# driver_piezo.net
KiCad netlist of a schematic drawn in EAGLE
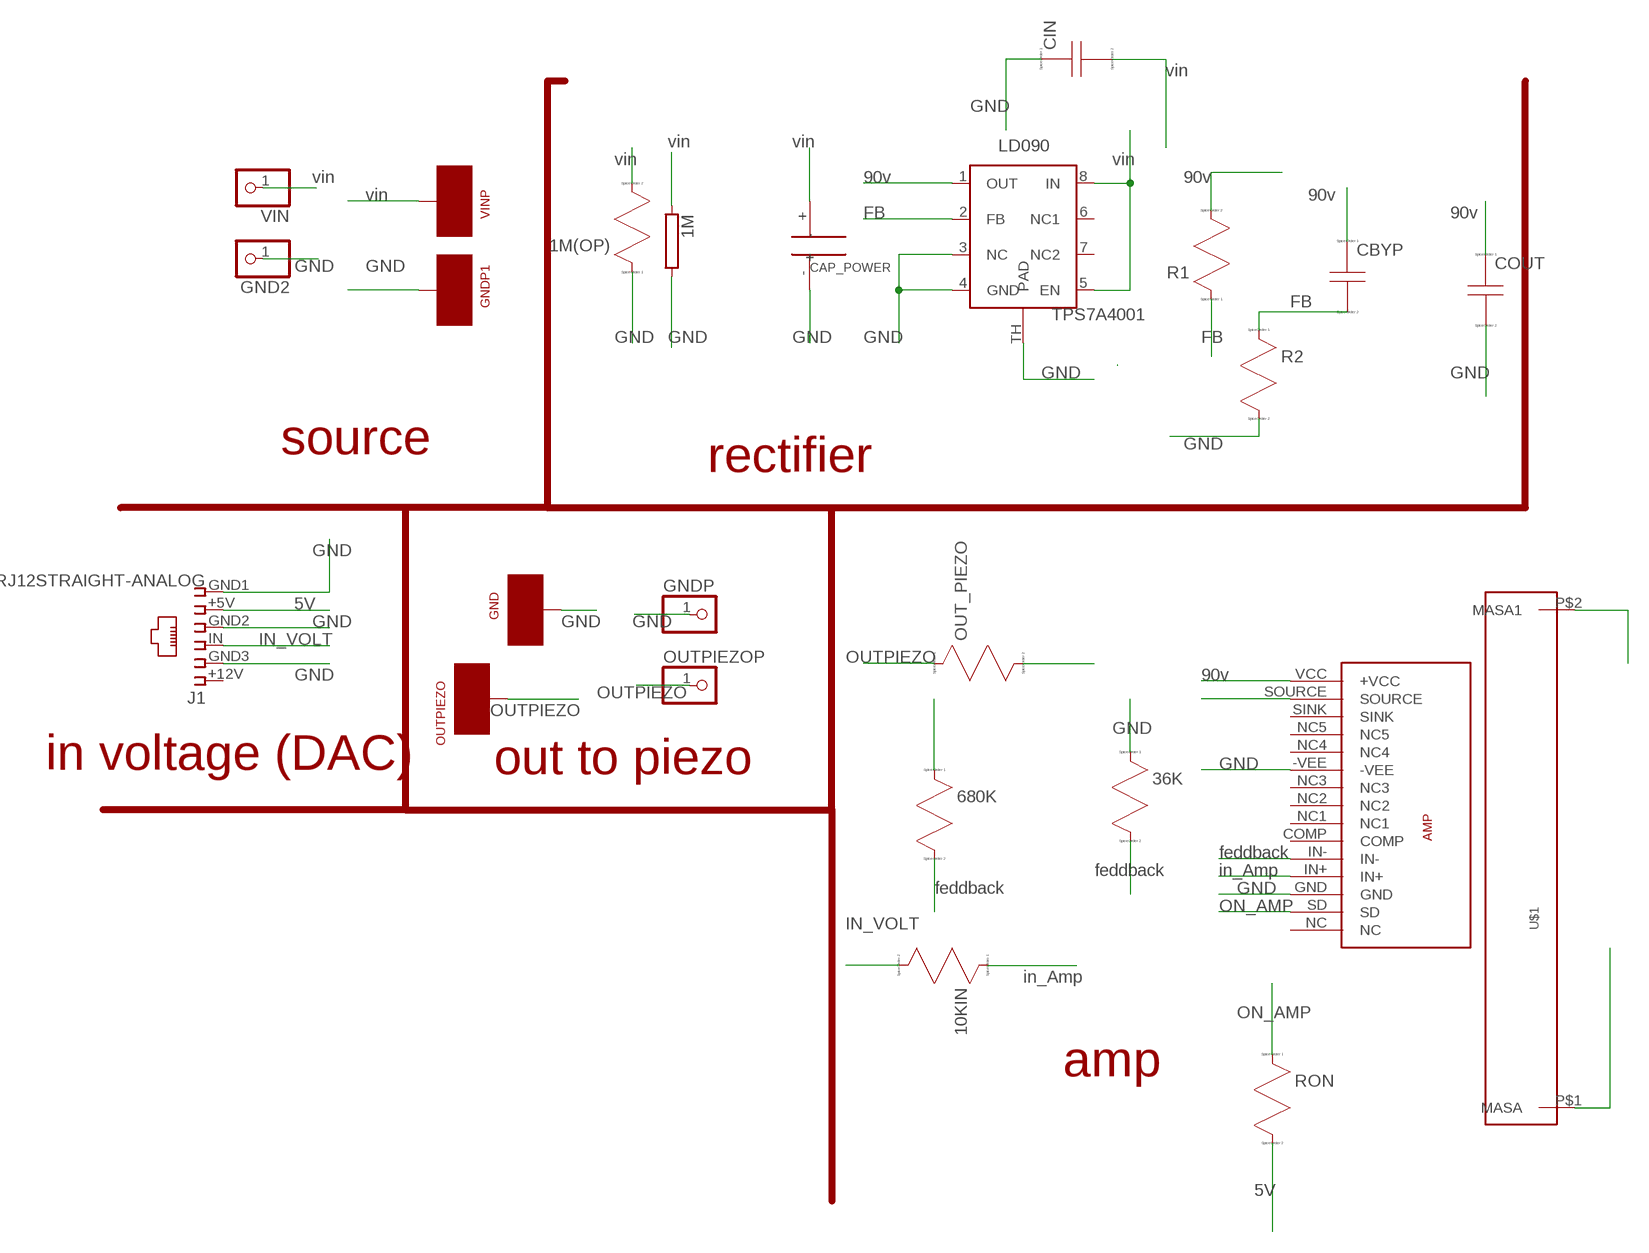
[diagram p0: schematic, sheet 1]

(export (version "E")
  (design (tool "Eeschema 10.0.6"))
  (components
    (comp (ref "1M")
      (value "RCA0002")
      (footprint "eagle-import:CA0002")
      (libsource (lib "eagle-import") (part "RCA0002"))
    )
    (comp (ref "1M(OP)")
      (value "RES")
      (footprint "eagle-import:R0805")
      (libsource (lib "eagle-import") (part "RES"))
    )
    (comp (ref "10KIN")
      (value "RES")
      (footprint "eagle-import:R0805")
      (libsource (lib "eagle-import") (part "RES"))
    )
    (comp (ref "36K")
      (value "RES")
      (footprint "eagle-import:R0805")
      (libsource (lib "eagle-import") (part "RES"))
    )
    (comp (ref "680K")
      (value "RES")
      (footprint "eagle-import:R0805")
      (libsource (lib "eagle-import") (part "RES"))
    )
    (comp (ref "AMP")
      (value "POWER_AMP_LME49811TB")
      (footprint "eagle-import:POWER_AMP_LME49811TB")
      (libsource (lib "eagle-import") (part "POWER_AMP_LME49811TB"))
    )
    (comp (ref "CAP_POWER")
      (value "CAP200VCAP200V")
      (footprint "eagle-import:CAP200V")
      (libsource (lib "eagle-import") (part "CAP200VCAP200V"))
    )
    (comp (ref "CBYP")
      (value "CAP")
      (footprint "eagle-import:C0805")
      (libsource (lib "eagle-import") (part "CAP"))
    )
    (comp (ref "CIN")
      (value "CAP")
      (footprint "eagle-import:C0805")
      (libsource (lib "eagle-import") (part "CAP"))
    )
    (comp (ref "COUT")
      (value "CAP")
      (footprint "eagle-import:C0805")
      (libsource (lib "eagle-import") (part "CAP"))
    )
    (comp (ref "GND")
      (value "PAD")
      (footprint "eagle-import:PAD")
      (libsource (lib "eagle-import") (part "PAD"))
    )
    (comp (ref "GND2")
      (value "PINHD-1X1")
      (footprint "eagle-import:1X01")
      (libsource (lib "eagle-import") (part "PINHD-1X1"))
    )
    (comp (ref "GNDP")
      (value "PINHD-1X1")
      (footprint "eagle-import:1X01")
      (libsource (lib "eagle-import") (part "PINHD-1X1"))
    )
    (comp (ref "GNDP1")
      (value "PAD")
      (footprint "eagle-import:PAD")
      (libsource (lib "eagle-import") (part "PAD"))
    )
    (comp (ref "J1")
      (value "RJ12STRAIGHT-ANALOG")
      (footprint "eagle-import:RJ12-STRAIGHT-ANALOG")
      (libsource (lib "eagle-import") (part "RJ12STRAIGHT-ANALOG"))
    )
    (comp (ref "LD090")
      (value "TPS7A4001")
      (footprint "eagle-import:S-PDSO-G08")
      (libsource (lib "eagle-import") (part "TPS7A4001"))
    )
    (comp (ref "OUTPIEZO")
      (value "PAD")
      (footprint "eagle-import:PAD")
      (libsource (lib "eagle-import") (part "PAD"))
    )
    (comp (ref "OUTPIEZOP")
      (value "PINHD-1X1")
      (footprint "eagle-import:1X01")
      (libsource (lib "eagle-import") (part "PINHD-1X1"))
    )
    (comp (ref "OUT_PIEZO")
      (value "RES")
      (footprint "eagle-import:R0805")
      (libsource (lib "eagle-import") (part "RES"))
    )
    (comp (ref "R1")
      (value "RES")
      (footprint "eagle-import:R0805")
      (libsource (lib "eagle-import") (part "RES"))
    )
    (comp (ref "R2")
      (value "RES")
      (footprint "eagle-import:R0805")
      (libsource (lib "eagle-import") (part "RES"))
    )
    (comp (ref "RON")
      (value "RES")
      (footprint "eagle-import:R0805")
      (libsource (lib "eagle-import") (part "RES"))
    )
    (comp (ref "U$1")
      (value "DISIPADOR")
      (footprint "eagle-import:DISIPADOR")
      (libsource (lib "eagle-import") (part "DISIPADOR"))
    )
    (comp (ref "VIN")
      (value "PINHD-1X1")
      (footprint "eagle-import:1X01")
      (libsource (lib "eagle-import") (part "PINHD-1X1"))
    )
    (comp (ref "VINP")
      (value "PAD")
      (footprint "eagle-import:PAD")
      (libsource (lib "eagle-import") (part "PAD"))
    )
  )
  (nets
    (net (code "1") (name "/5V") (class "Default")
      (node (ref "J1") (pin "+5V") (pinfunction "5_+5V") (pintype "bidirectional"))
      (node (ref "RON") (pin "2") (pinfunction "B_2") (pintype "passive"))
    )
    (net (code "2") (name "/B") (class "Default")
      (node (ref "36K") (pin "2") (pinfunction "B_2") (pintype "passive"))
      (node (ref "680K") (pin "2") (pinfunction "B_2") (pintype "passive"))
      (node (ref "AMP") (pin "IN-") (pinfunction "IN-_IN-") (pintype "bidirectional"))
    )
    (net (code "3") (name "/FB") (class "Default")
      (node (ref "CBYP") (pin "2") (pinfunction "B_2") (pintype "passive"))
      (node (ref "LD090") (pin "2") (pinfunction "FB_2") (pintype "passive"))
      (node (ref "R1") (pin "1") (pinfunction "A_1") (pintype "passive"))
      (node (ref "R2") (pin "1") (pinfunction "A_1") (pintype "passive"))
    )
    (net (code "4") (name "/GND") (class "Default")
      (node (ref "1M") (pin "2") (pinfunction "2_2") (pintype "passive"))
      (node (ref "1M(OP)") (pin "1") (pinfunction "A_1") (pintype "passive"))
      (node (ref "36K") (pin "1") (pinfunction "A_1") (pintype "passive"))
      (node (ref "AMP") (pin "-VEE") (pinfunction "-VEE_-VEE") (pintype "bidirectional"))
      (node (ref "AMP") (pin "GND") (pinfunction "GND_GND") (pintype "bidirectional"))
      (node (ref "CAP_POWER") (pin "-") (pinfunction "-_-") (pintype "bidirectional"))
      (node (ref "CIN") (pin "1") (pinfunction "A_1") (pintype "passive"))
      (node (ref "COUT") (pin "2") (pinfunction "B_2") (pintype "passive"))
      (node (ref "GND") (pin "P$1") (pinfunction "2_P$1") (pintype "bidirectional"))
      (node (ref "GND2") (pin "1") (pinfunction "1_1") (pintype "passive"))
      (node (ref "GNDP") (pin "1") (pinfunction "1_1") (pintype "passive"))
      (node (ref "GNDP1") (pin "P$1") (pinfunction "2_P$1") (pintype "bidirectional"))
      (node (ref "J1") (pin "GND1") (pinfunction "6_GND1") (pintype "bidirectional"))
      (node (ref "J1") (pin "GND2") (pinfunction "4_GND2") (pintype "bidirectional"))
      (node (ref "J1") (pin "GND3") (pinfunction "2_GND3") (pintype "bidirectional"))
      (node (ref "LD090") (pin "3") (pinfunction "NC_3") (pintype "input"))
      (node (ref "LD090") (pin "4") (pinfunction "GND_4") (pintype "power_in"))
      (node (ref "LD090") (pin "TH") (pinfunction "PAD_TH") (pintype "bidirectional"))
      (node (ref "R2") (pin "2") (pinfunction "B_2") (pintype "passive"))
      (node (ref "U$1") (pin "P$1") (pinfunction "MASA_P$1") (pintype "bidirectional"))
      (node (ref "U$1") (pin "P$2") (pinfunction "MASA1_P$2") (pintype "bidirectional"))
    )
    (net (code "5") (name "/IN_AMP") (class "Default")
      (node (ref "10KIN") (pin "1") (pinfunction "A_1") (pintype "passive"))
      (node (ref "AMP") (pin "IN+") (pinfunction "IN+_IN+") (pintype "bidirectional"))
    )
    (net (code "6") (name "/IN_VOLTAGE") (class "Default")
      (node (ref "10KIN") (pin "2") (pinfunction "B_2") (pintype "passive"))
      (node (ref "J1") (pin "IN") (pinfunction "3_IN") (pintype "bidirectional"))
    )
    (net (code "7") (name "/ON") (class "Default")
      (node (ref "AMP") (pin "SD") (pinfunction "SD_SD") (pintype "bidirectional"))
      (node (ref "RON") (pin "1") (pinfunction "A_1") (pintype "passive"))
    )
    (net (code "8") (name "/OUT_PIEZO") (class "Default")
      (node (ref "OUTPIEZO") (pin "P$1") (pinfunction "2_P$1") (pintype "bidirectional"))
      (node (ref "OUTPIEZOP") (pin "1") (pinfunction "1_1") (pintype "passive"))
      (node (ref "OUT_PIEZO") (pin "1") (pinfunction "A_1") (pintype "passive"))
    )
    (net (code "9") (name "/SOURCE") (class "Default")
      (node (ref "680K") (pin "1") (pinfunction "A_1") (pintype "passive"))
      (node (ref "AMP") (pin "SOURCE") (pinfunction "SOURCE_SOURCE") (pintype "bidirectional"))
      (node (ref "OUT_PIEZO") (pin "2") (pinfunction "B_2") (pintype "passive"))
    )
    (net (code "10") (name "/V90") (class "Default")
      (node (ref "AMP") (pin "VCC") (pinfunction "+VCC_VCC") (pintype "bidirectional"))
      (node (ref "CBYP") (pin "1") (pinfunction "A_1") (pintype "passive"))
      (node (ref "COUT") (pin "1") (pinfunction "A_1") (pintype "passive"))
      (node (ref "LD090") (pin "1") (pinfunction "OUT_1") (pintype "input"))
      (node (ref "R1") (pin "2") (pinfunction "B_2") (pintype "passive"))
    )
    (net (code "11") (name "/VIN") (class "Default")
      (node (ref "1M") (pin "1") (pinfunction "1_1") (pintype "passive"))
      (node (ref "1M(OP)") (pin "2") (pinfunction "B_2") (pintype "passive"))
      (node (ref "CAP_POWER") (pin "+") (pinfunction "+_+") (pintype "bidirectional"))
      (node (ref "CIN") (pin "2") (pinfunction "B_2") (pintype "passive"))
      (node (ref "LD090") (pin "5") (pinfunction "EN_5") (pintype "input"))
      (node (ref "LD090") (pin "8") (pinfunction "IN_8") (pintype "input"))
      (node (ref "VIN") (pin "1") (pinfunction "1_1") (pintype "passive"))
      (node (ref "VINP") (pin "P$1") (pinfunction "2_P$1") (pintype "bidirectional"))
    )
    (net (code "12") (name "unconnected-(AMP-PadCOMP)") (class "Default")
      (node (ref "AMP") (pin "COMP") (pinfunction "COMP_COMP") (pintype "bidirectional"))
    )
    (net (code "13") (name "unconnected-(AMP-PadNC)") (class "Default")
      (node (ref "AMP") (pin "NC") (pinfunction "NC_NC") (pintype "bidirectional"))
    )
    (net (code "14") (name "unconnected-(AMP-PadNC1)") (class "Default")
      (node (ref "AMP") (pin "NC1") (pinfunction "NC1_NC1") (pintype "bidirectional"))
    )
    (net (code "15") (name "unconnected-(AMP-PadNC2)") (class "Default")
      (node (ref "AMP") (pin "NC2") (pinfunction "NC2_NC2") (pintype "bidirectional"))
    )
    (net (code "16") (name "unconnected-(AMP-PadNC3)") (class "Default")
      (node (ref "AMP") (pin "NC3") (pinfunction "NC3_NC3") (pintype "bidirectional"))
    )
    (net (code "17") (name "unconnected-(AMP-PadNC4)") (class "Default")
      (node (ref "AMP") (pin "NC4") (pinfunction "NC4_NC4") (pintype "bidirectional"))
    )
    (net (code "18") (name "unconnected-(AMP-PadNC5)") (class "Default")
      (node (ref "AMP") (pin "NC5") (pinfunction "NC5_NC5") (pintype "bidirectional"))
    )
    (net (code "19") (name "unconnected-(AMP-PadSINK)") (class "Default")
      (node (ref "AMP") (pin "SINK") (pinfunction "SINK_SINK") (pintype "bidirectional"))
    )
    (net (code "20") (name "unconnected-(J1-1-Pad+12V)") (class "Default")
      (node (ref "J1") (pin "+12V") (pinfunction "1_+12V") (pintype "bidirectional"))
    )
    (net (code "21") (name "unconnected-(LD090-NC1-Pad6)") (class "Default")
      (node (ref "LD090") (pin "6") (pinfunction "NC1_6") (pintype "output"))
    )
    (net (code "22") (name "unconnected-(LD090-NC2-Pad7)") (class "Default")
      (node (ref "LD090") (pin "7") (pinfunction "NC2_7") (pintype "input"))
    )
  )
)
